# multi-pcb-power_v1.net
KiCad netlist of a schematic drawn in EAGLE
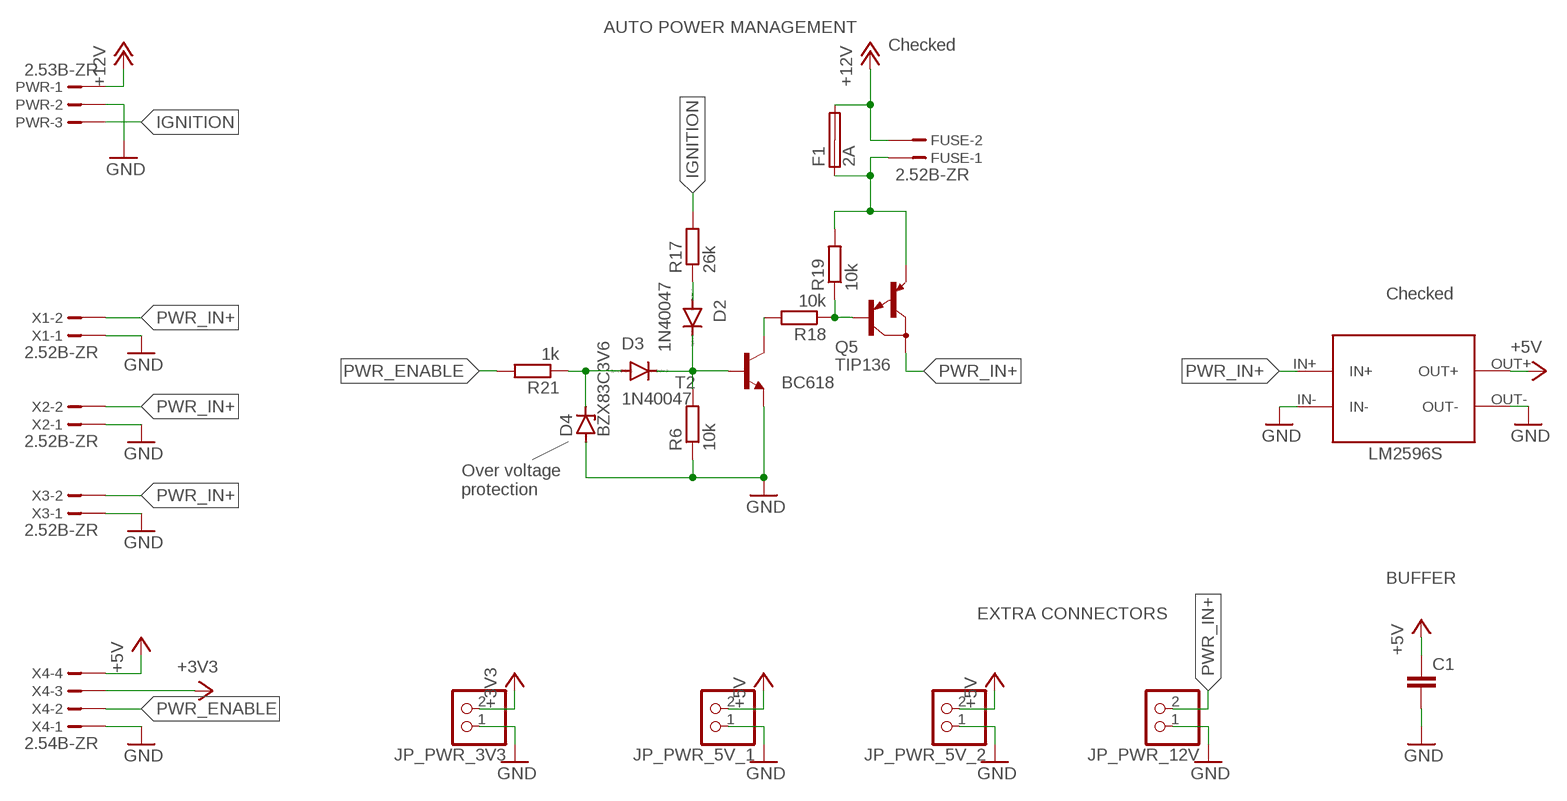
[diagram p0: schematic, sheet 1]

(export (version "E")
  (design (tool "Eeschema 10.0.6"))
  (components
    (comp (ref "C1")
      (value "C-EU050-075X075")
      (footprint "eagle-import:C050-075X075")
      (libsource (lib "eagle-import") (part "C-EU050-075X075"))
    )
    (comp (ref "D2")
      (value "1N40047")
      (footprint "eagle-import:DO41-7.6")
      (libsource (lib "eagle-import") (part "1N40047"))
    )
    (comp (ref "D3")
      (value "1N40047")
      (footprint "eagle-import:DO41-7.6")
      (libsource (lib "eagle-import") (part "1N40047"))
    )
    (comp (ref "D4")
      (value "BZX83C3V6")
      (footprint "eagle-import:DO41Z7.6")
      (libsource (lib "eagle-import") (part "BZX857"))
    )
    (comp (ref "F1")
      (value "2A")
      (footprint "eagle-import:SHK20L")
      (libsource (lib "eagle-import") (part "SHK20L"))
    )
    (comp (ref "FUSE")
      (value "2.52B-ZR")
      (footprint "eagle-import:B2B-ZR2.5")
      (libsource (lib "eagle-import") (part "?2B-ZR2.5"))
    )
    (comp (ref "JP_PWR_3V3")
      (value "PINHD-1X2")
      (footprint "eagle-import:1X02")
      (libsource (lib "eagle-import") (part "PINHD-1X2"))
    )
    (comp (ref "JP_PWR_5V_1")
      (value "PINHD-1X2")
      (footprint "eagle-import:1X02")
      (libsource (lib "eagle-import") (part "PINHD-1X2"))
    )
    (comp (ref "JP_PWR_5V_2")
      (value "PINHD-1X2")
      (footprint "eagle-import:1X02")
      (libsource (lib "eagle-import") (part "PINHD-1X2"))
    )
    (comp (ref "JP_PWR_12V")
      (value "PINHD-1X2")
      (footprint "eagle-import:1X02")
      (libsource (lib "eagle-import") (part "PINHD-1X2"))
    )
    (comp (ref "PWR")
      (value "2.53B-ZR")
      (footprint "eagle-import:B3B-ZR2.5")
      (libsource (lib "eagle-import") (part "?3B-ZR2.5"))
    )
    (comp (ref "Q5")
      (value "TIP136")
      (footprint "eagle-import:TO220")
      (libsource (lib "eagle-import") (part "TIP136"))
    )
    (comp (ref "R6")
      (value "10k")
      (footprint "eagle-import:0207_7")
      (libsource (lib "eagle-import") (part "R-EU_0207/7"))
    )
    (comp (ref "R17")
      (value "26k")
      (footprint "eagle-import:0207_10")
      (libsource (lib "eagle-import") (part "R-EU_0207/10"))
    )
    (comp (ref "R18")
      (value "10k")
      (footprint "eagle-import:0207_10")
      (libsource (lib "eagle-import") (part "R-EU_0207/10"))
    )
    (comp (ref "R19")
      (value "10k")
      (footprint "eagle-import:0207_10")
      (libsource (lib "eagle-import") (part "R-EU_0207/10"))
    )
    (comp (ref "R21")
      (value "1k")
      (footprint "eagle-import:0207_10")
      (libsource (lib "eagle-import") (part "R-EU_0207/10"))
    )
    (comp (ref "T2")
      (value "BC618")
      (footprint "eagle-import:TO92-EBC")
      (libsource (lib "eagle-import") (part "BC618"))
    )
    (comp (ref "U$4")
      (value "LM2596S")
      (footprint "eagle-import:LM2596S")
      (libsource (lib "eagle-import") (part "LM2596S"))
    )
    (comp (ref "X1")
      (value "2.52B-ZR")
      (footprint "eagle-import:B2B-ZR2.5")
      (libsource (lib "eagle-import") (part "?2B-ZR2.5"))
    )
    (comp (ref "X2")
      (value "2.52B-ZR")
      (footprint "eagle-import:B2B-ZR2.5")
      (libsource (lib "eagle-import") (part "?2B-ZR2.5"))
    )
    (comp (ref "X3")
      (value "2.52B-ZR")
      (footprint "eagle-import:B2B-ZR2.5")
      (libsource (lib "eagle-import") (part "?2B-ZR2.5"))
    )
    (comp (ref "X4")
      (value "2.54B-ZR")
      (footprint "eagle-import:B4B-ZR2.5")
      (libsource (lib "eagle-import") (part "?4B-ZR2.5"))
    )
  )
  (nets
    (net (code "1") (name "+3V3") (class "Default")
      (node (ref "JP_PWR_3V3") (pin "2") (pinfunction "2_2") (pintype "passive"))
      (node (ref "X4") (pin "3") (pinfunction "1_3") (pintype "passive"))
    )
    (net (code "2") (name "+5V") (class "Default")
      (node (ref "C1") (pin "1") (pinfunction "1_1") (pintype "passive"))
      (node (ref "JP_PWR_5V_1") (pin "2") (pinfunction "2_2") (pintype "passive"))
      (node (ref "JP_PWR_5V_2") (pin "2") (pinfunction "2_2") (pintype "passive"))
      (node (ref "U$4") (pin "OUT+") (pinfunction "OUT+_OUT+") (pintype "bidirectional"))
      (node (ref "X4") (pin "4") (pinfunction "1_4") (pintype "passive"))
    )
    (net (code "3") (name "+12V") (class "Default")
      (node (ref "F1") (pin "2A") (pinfunction "2A_2A") (pintype "passive"))
      (node (ref "FUSE") (pin "2") (pinfunction "1_2") (pintype "passive"))
      (node (ref "PWR") (pin "1") (pinfunction "1_1") (pintype "passive"))
    )
    (net (code "4") (name "GND") (class "Default")
      (node (ref "C1") (pin "2") (pinfunction "2_2") (pintype "passive"))
      (node (ref "D4") (pin "A") (pinfunction "A_A") (pintype "passive"))
      (node (ref "JP_PWR_12V") (pin "1") (pinfunction "1_1") (pintype "passive"))
      (node (ref "JP_PWR_3V3") (pin "1") (pinfunction "1_1") (pintype "passive"))
      (node (ref "JP_PWR_5V_1") (pin "1") (pinfunction "1_1") (pintype "passive"))
      (node (ref "JP_PWR_5V_2") (pin "1") (pinfunction "1_1") (pintype "passive"))
      (node (ref "PWR") (pin "2") (pinfunction "1_2") (pintype "passive"))
      (node (ref "R6") (pin "1") (pinfunction "1_1") (pintype "passive"))
      (node (ref "T2") (pin "E") (pinfunction "E_E") (pintype "passive"))
      (node (ref "U$4") (pin "IN-") (pinfunction "IN-_IN-") (pintype "bidirectional"))
      (node (ref "U$4") (pin "OUT-") (pinfunction "OUT-_OUT-") (pintype "bidirectional"))
      (node (ref "X1") (pin "1") (pinfunction "1_1") (pintype "passive"))
      (node (ref "X2") (pin "1") (pinfunction "1_1") (pintype "passive"))
      (node (ref "X3") (pin "1") (pinfunction "1_1") (pintype "passive"))
      (node (ref "X4") (pin "1") (pinfunction "1_1") (pintype "passive"))
    )
    (net (code "5") (name "IGNITION") (class "Default")
      (node (ref "PWR") (pin "3") (pinfunction "1_3") (pintype "passive"))
      (node (ref "R17") (pin "2") (pinfunction "2_2") (pintype "passive"))
    )
    (net (code "6") (name "Net-(D2-PadA)") (class "Default")
      (node (ref "D2") (pin "A") (pinfunction "A_A") (pintype "passive"))
      (node (ref "R17") (pin "1") (pinfunction "1_1") (pintype "passive"))
    )
    (net (code "7") (name "Net-(D2-PadC)") (class "Default")
      (node (ref "D2") (pin "C") (pinfunction "C_C") (pintype "passive"))
      (node (ref "D3") (pin "C") (pinfunction "C_C") (pintype "passive"))
      (node (ref "R6") (pin "2") (pinfunction "2_2") (pintype "passive"))
      (node (ref "T2") (pin "B") (pinfunction "B_B") (pintype "passive"))
    )
    (net (code "8") (name "Net-(D3-PadA)") (class "Default")
      (node (ref "D3") (pin "A") (pinfunction "A_A") (pintype "passive"))
      (node (ref "D4") (pin "C") (pinfunction "C_C") (pintype "passive"))
      (node (ref "R21") (pin "1") (pinfunction "1_1") (pintype "passive"))
    )
    (net (code "9") (name "Net-(Q5-B)") (class "Default")
      (node (ref "Q5") (pin "1") (pinfunction "B_1") (pintype "passive"))
      (node (ref "R18") (pin "1") (pinfunction "1_1") (pintype "passive"))
      (node (ref "R19") (pin "1") (pinfunction "1_1") (pintype "passive"))
    )
    (net (code "10") (name "Net-(Q5-E)") (class "Default")
      (node (ref "F1") (pin "1A") (pinfunction "1A_1A") (pintype "passive"))
      (node (ref "FUSE") (pin "1") (pinfunction "1_1") (pintype "passive"))
      (node (ref "Q5") (pin "3") (pinfunction "E_3") (pintype "passive"))
      (node (ref "R19") (pin "2") (pinfunction "2_2") (pintype "passive"))
    )
    (net (code "11") (name "Net-(R18-Pad2)") (class "Default")
      (node (ref "R18") (pin "2") (pinfunction "2_2") (pintype "passive"))
      (node (ref "T2") (pin "C") (pinfunction "C_C") (pintype "passive"))
    )
    (net (code "12") (name "PWR_ENABLE") (class "Default")
      (node (ref "R21") (pin "2") (pinfunction "2_2") (pintype "passive"))
      (node (ref "X4") (pin "2") (pinfunction "1_2") (pintype "passive"))
    )
    (net (code "13") (name "PWR_IN+") (class "Default")
      (node (ref "JP_PWR_12V") (pin "2") (pinfunction "2_2") (pintype "passive"))
      (node (ref "Q5") (pin "2") (pinfunction "C_2") (pintype "passive"))
      (node (ref "U$4") (pin "IN+") (pinfunction "IN+_IN+") (pintype "bidirectional"))
      (node (ref "X1") (pin "2") (pinfunction "1_2") (pintype "passive"))
      (node (ref "X2") (pin "2") (pinfunction "1_2") (pintype "passive"))
      (node (ref "X3") (pin "2") (pinfunction "1_2") (pintype "passive"))
    )
    (net (code "14") (name "unconnected-(F1-Pad1B)") (class "Default")
      (node (ref "F1") (pin "1B") (pinfunction "1B_1B") (pintype "passive"))
    )
    (net (code "15") (name "unconnected-(F1-Pad2B)") (class "Default")
      (node (ref "F1") (pin "2B") (pinfunction "2B_2B") (pintype "passive"))
    )
  )
)
